# Sheet1.net
KiCad netlist of a schematic drawn in Altium Designer
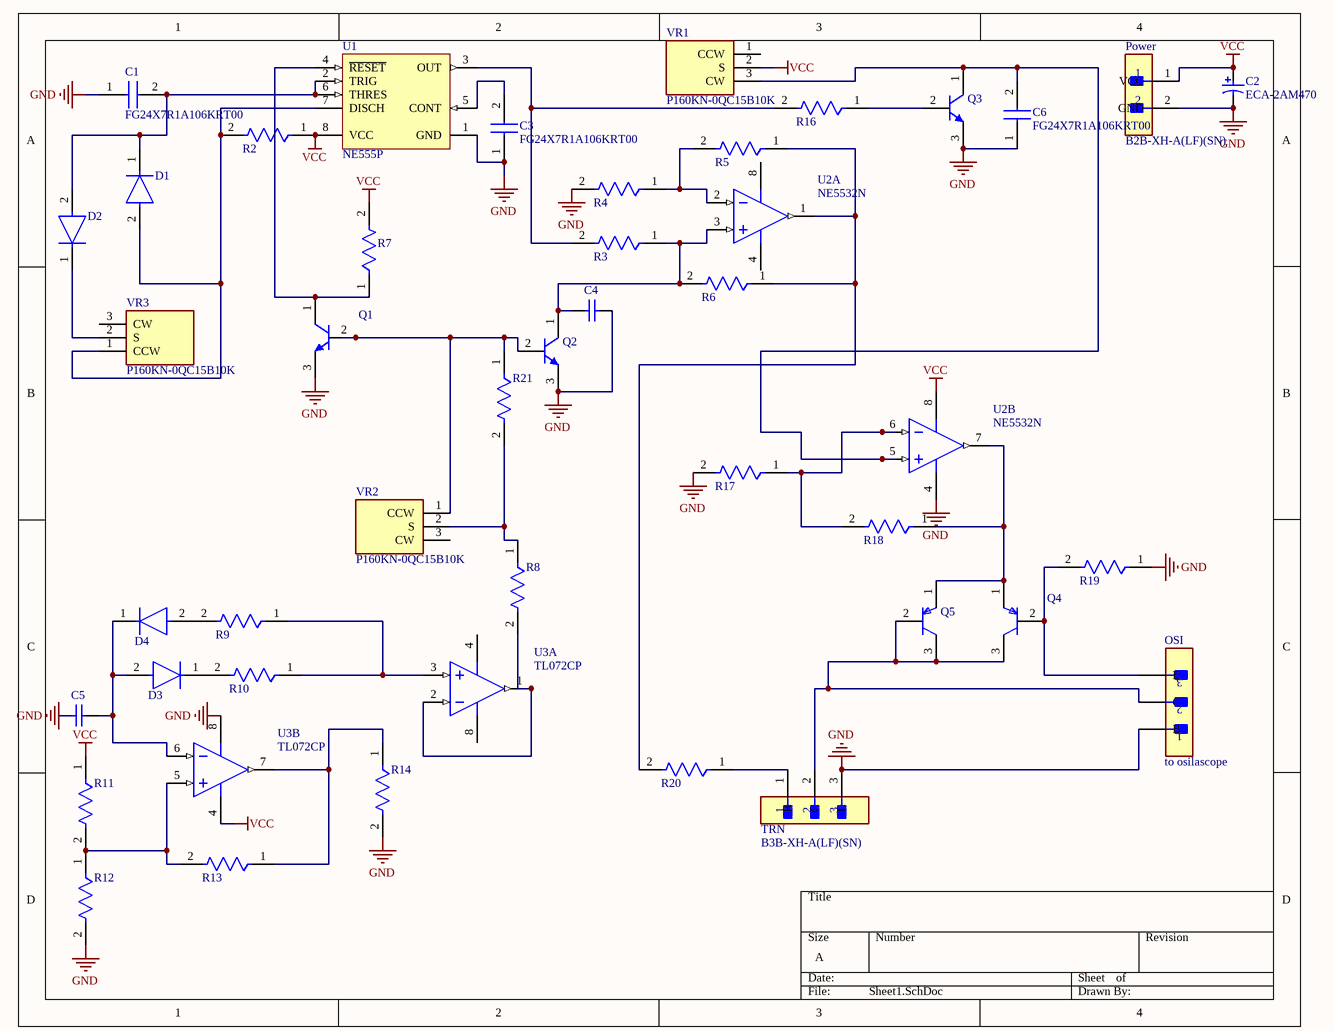
[diagram p0: Sheet1.SchDoc]

(export (version "E")
  (design (tool "Eeschema 10.0.6"))
  (components
    (comp (ref "C1")
      (value "FG24X7R1A106KRT00")
      (footprint "SamacSys:FG24")
      (description "Capacitor")
      (fields (field (name "MOUSER PART NUMBER") "810-FG24X7R1A106KRT0"))
      (libsource (lib "*") (part "FG24X7R1A106KRT00"))
    )
    (comp (ref "C2")
      (value "ECA-2AM470")
      (footprint "CAPPR65-350-1150X800X1250")
      (description "Aluminum Electrolytic Capacitor, 47 uF, +/- 20%, 100 V, -40 to 85 degC, 2-Pin THD, RoHS, Bulk")
      (libsource (lib "Altium Content Vault") (part "CAP-P-2"))
    )
    (comp (ref "C3")
      (value "FG24X7R1A106KRT00")
      (footprint "SamacSys:FG24")
      (description "Capacitor")
      (fields (field (name "MOUSER PART NUMBER") "810-FG24X7R1A106KRT0"))
      (libsource (lib "*") (part "FG24X7R1A106KRT00"))
    )
    (comp (ref "C4")
      (value "SA115C104KAR")
      (footprint "AVX-SA115C104KAR")
      (fields (field (name "TOLERANCE") "±10%") (field (name "MANUFACTURER") "AVX"))
      (libsource (lib "Altium Content Vault") (part "CAP-NP-2"))
    )
    (comp (ref "C5")
      (value "SA115C104KAR")
      (footprint "AVX-SA115C104KAR")
      (fields (field (name "TOLERANCE") "±10%") (field (name "MANUFACTURER") "AVX"))
      (libsource (lib "Altium Content Vault") (part "CAP-NP-2"))
    )
    (comp (ref "C6")
      (value "FG24X7R1A106KRT00")
      (footprint "SamacSys:FG24")
      (description "Capacitor")
      (fields (field (name "MOUSER PART NUMBER") "810-FG24X7R1A106KRT0"))
      (libsource (lib "*") (part "FG24X7R1A106KRT00"))
    )
    (comp (ref "D1")
      (value "1N4001-E3/54")
      (footprint "FP-1N4001-E3-54-MFG")
      (description "DIODE GEN PURP 50V 1A DO204AL")
      (fields (field (name "VOLTAGE") "50V"))
      (libsource (lib "Altium Content Vault") (part "d7152d700b627762746794eb795d46e"))
    )
    (comp (ref "D2")
      (value "1N4001-E3/54")
      (footprint "FP-1N4001-E3-54-MFG")
      (description "DIODE GEN PURP 50V 1A DO204AL")
      (fields (field (name "VOLTAGE") "50V"))
      (libsource (lib "Altium Content Vault") (part "d7152d700b627762746794eb795d46e"))
    )
    (comp (ref "D3")
      (value "1N4001-E3/54")
      (footprint "FP-1N4001-E3-54-MFG")
      (description "DIODE GEN PURP 50V 1A DO204AL")
      (fields (field (name "VOLTAGE") "50V"))
      (libsource (lib "Altium Content Vault") (part "d7152d700b627762746794eb795d46e"))
    )
    (comp (ref "D4")
      (value "1N4001-E3/54")
      (footprint "FP-1N4001-E3-54-MFG")
      (description "DIODE GEN PURP 50V 1A DO204AL")
      (fields (field (name "VOLTAGE") "50V"))
      (libsource (lib "Altium Content Vault") (part "d7152d700b627762746794eb795d46e"))
    )
    (comp (ref "OSI")
      (value "to osilascope")
      (footprint "FP-B3B-XH-A_LF_SN-MFG")
      (description "CONN HEADER VERT 3POS 2.5MM")
      (libsource (lib "") (part "0d3f023dd272f625e17a2be33dea85f_1"))
    )
    (comp (ref "Power")
      (value "B2B-XH-A(LF)(SN)")
      (footprint "FP-B2B-XH-A_LF_SN-MFG")
      (description "CONN HEADER VERT 2POS 2.5MM")
      (libsource (lib "Altium Content Vault") (part "3bc925449376181038e59eaffc5286c"))
    )
    (comp (ref "Q1")
      (value "P2N2222ARL1G")
      (footprint "ONSC-TO-92-3-29-11_AM_BL")
      (description "Amplifier Transistor, NPN Silicon, 3-Pin TO-92, Pb-Free, Tape and Reel")
      (fields (field (name "MANUFACTURER") "On Semiconductor"))
      (libsource (lib "Altium Content Vault") (part "ONSC-NPN-C1B2E3-3"))
    )
    (comp (ref "Q2")
      (value "P2N2222ARL1G")
      (footprint "ONSC-TO-92-3-29-11_AM_BL")
      (description "Amplifier Transistor, NPN Silicon, 3-Pin TO-92, Pb-Free, Tape and Reel")
      (fields (field (name "MANUFACTURER") "On Semiconductor"))
      (libsource (lib "Altium Content Vault") (part "ONSC-NPN-C1B2E3-3"))
    )
    (comp (ref "Q3")
      (value "P2N2222ARL1G")
      (footprint "ONSC-TO-92-3-29-11_AM_BL")
      (description "Amplifier Transistor, NPN Silicon, 3-Pin TO-92, Pb-Free, Tape and Reel")
      (fields (field (name "MANUFACTURER") "On Semiconductor"))
      (libsource (lib "Altium Content Vault") (part "ONSC-NPN-C1B2E3-3"))
    )
    (comp (ref "Q4")
      (value "2N3906TF")
      (footprint "FP-135AR-MFG")
      (description "2N3906TF Small Signal Bipolar Transistor, 0.2A I(C), 40V V(BR)CEO, 1-Element, PNP, Silicon, TO-92")
      (libsource (lib "Altium Content Vault") (part "40d2b7e180a7bcff784209620afba3e"))
    )
    (comp (ref "Q5")
      (value "2N3906TF")
      (footprint "FP-135AR-MFG")
      (description "2N3906TF Small Signal Bipolar Transistor, 0.2A I(C), 40V V(BR)CEO, 1-Element, PNP, Silicon, TO-92")
      (libsource (lib "Altium Content Vault") (part "40d2b7e180a7bcff784209620afba3e"))
    )
    (comp (ref "R2")
      (value "MRS16000C2002FCT00")
      (footprint "FP-MRS1600-MFG")
      (description "RES 20K OHM 0.4W 1% AXIAL")
      (fields (field (name "TOLERANCE") "1%"))
      (libsource (lib "Altium Content Vault") (part "1029c3af85768c4190bb7ad29bc67b5"))
    )
    (comp (ref "R3")
      (value "MRS16000C2002FCT00")
      (footprint "FP-MRS1600-MFG")
      (description "RES 20K OHM 0.4W 1% AXIAL")
      (fields (field (name "TOLERANCE") "1%"))
      (libsource (lib "Altium Content Vault") (part "1029c3af85768c4190bb7ad29bc67b5"))
    )
    (comp (ref "R4")
      (value "MRS16000C2002FCT00")
      (footprint "FP-MRS1600-MFG")
      (description "RES 20K OHM 0.4W 1% AXIAL")
      (fields (field (name "TOLERANCE") "1%"))
      (libsource (lib "Altium Content Vault") (part "1029c3af85768c4190bb7ad29bc67b5"))
    )
    (comp (ref "R5")
      (value "MRS16000C2002FCT00")
      (footprint "FP-MRS1600-MFG")
      (description "RES 20K OHM 0.4W 1% AXIAL")
      (fields (field (name "TOLERANCE") "1%"))
      (libsource (lib "Altium Content Vault") (part "1029c3af85768c4190bb7ad29bc67b5"))
    )
    (comp (ref "R6")
      (value "MRS16000C2002FCT00")
      (footprint "FP-MRS1600-MFG")
      (description "RES 20K OHM 0.4W 1% AXIAL")
      (fields (field (name "TOLERANCE") "1%"))
      (libsource (lib "Altium Content Vault") (part "1029c3af85768c4190bb7ad29bc67b5"))
    )
    (comp (ref "R7")
      (value "MRS16000C2002FCT00")
      (footprint "FP-MRS1600-MFG")
      (description "RES 20K OHM 0.4W 1% AXIAL")
      (fields (field (name "TOLERANCE") "1%"))
      (libsource (lib "Altium Content Vault") (part "1029c3af85768c4190bb7ad29bc67b5"))
    )
    (comp (ref "R8")
      (value "MRS16000C2002FCT00")
      (footprint "FP-MRS1600-MFG")
      (description "RES 20K OHM 0.4W 1% AXIAL")
      (fields (field (name "TOLERANCE") "1%"))
      (libsource (lib "Altium Content Vault") (part "1029c3af85768c4190bb7ad29bc67b5"))
    )
    (comp (ref "R9")
      (value "MRS16000C2002FCT00")
      (footprint "FP-MRS1600-MFG")
      (description "RES 20K OHM 0.4W 1% AXIAL")
      (fields (field (name "TOLERANCE") "1%"))
      (libsource (lib "Altium Content Vault") (part "1029c3af85768c4190bb7ad29bc67b5"))
    )
    (comp (ref "R10")
      (value "MRS16000C2002FCT00")
      (footprint "FP-MRS1600-MFG")
      (description "RES 20K OHM 0.4W 1% AXIAL")
      (fields (field (name "TOLERANCE") "1%"))
      (libsource (lib "Altium Content Vault") (part "1029c3af85768c4190bb7ad29bc67b5"))
    )
    (comp (ref "R11")
      (value "MRS16000C2002FCT00")
      (footprint "FP-MRS1600-MFG")
      (description "RES 20K OHM 0.4W 1% AXIAL")
      (fields (field (name "TOLERANCE") "1%"))
      (libsource (lib "Altium Content Vault") (part "1029c3af85768c4190bb7ad29bc67b5"))
    )
    (comp (ref "R12")
      (value "MRS16000C2002FCT00")
      (footprint "FP-MRS1600-MFG")
      (description "RES 20K OHM 0.4W 1% AXIAL")
      (fields (field (name "TOLERANCE") "1%"))
      (libsource (lib "Altium Content Vault") (part "1029c3af85768c4190bb7ad29bc67b5"))
    )
    (comp (ref "R13")
      (value "MRS16000C2002FCT00")
      (footprint "FP-MRS1600-MFG")
      (description "RES 20K OHM 0.4W 1% AXIAL")
      (fields (field (name "TOLERANCE") "1%"))
      (libsource (lib "Altium Content Vault") (part "1029c3af85768c4190bb7ad29bc67b5"))
    )
    (comp (ref "R14")
      (value "MRS16000C2002FCT00")
      (footprint "FP-MRS1600-MFG")
      (description "RES 20K OHM 0.4W 1% AXIAL")
      (fields (field (name "TOLERANCE") "1%"))
      (libsource (lib "Altium Content Vault") (part "1029c3af85768c4190bb7ad29bc67b5"))
    )
    (comp (ref "R16")
      (value "MRS16000C2002FCT00")
      (footprint "FP-MRS1600-MFG")
      (description "RES 20K OHM 0.4W 1% AXIAL")
      (fields (field (name "TOLERANCE") "1%"))
      (libsource (lib "Altium Content Vault") (part "1029c3af85768c4190bb7ad29bc67b5"))
    )
    (comp (ref "R17")
      (value "MRS16000C2002FCT00")
      (footprint "FP-MRS1600-MFG")
      (description "RES 20K OHM 0.4W 1% AXIAL")
      (fields (field (name "TOLERANCE") "1%"))
      (libsource (lib "Altium Content Vault") (part "1029c3af85768c4190bb7ad29bc67b5"))
    )
    (comp (ref "R18")
      (value "MRS16000C2002FCT00")
      (footprint "FP-MRS1600-MFG")
      (description "RES 20K OHM 0.4W 1% AXIAL")
      (fields (field (name "TOLERANCE") "1%"))
      (libsource (lib "Altium Content Vault") (part "1029c3af85768c4190bb7ad29bc67b5"))
    )
    (comp (ref "R19")
      (value "MRS16000C2002FCT00")
      (footprint "FP-MRS1600-MFG")
      (description "RES 20K OHM 0.4W 1% AXIAL")
      (fields (field (name "TOLERANCE") "1%"))
      (libsource (lib "Altium Content Vault") (part "1029c3af85768c4190bb7ad29bc67b5"))
    )
    (comp (ref "R20")
      (value "MRS16000C2002FCT00")
      (footprint "FP-MRS1600-MFG")
      (description "RES 20K OHM 0.4W 1% AXIAL")
      (fields (field (name "TOLERANCE") "1%"))
      (libsource (lib "Altium Content Vault") (part "1029c3af85768c4190bb7ad29bc67b5"))
    )
    (comp (ref "R21")
      (value "MRS16000C2002FCT00")
      (footprint "FP-MRS1600-MFG")
      (description "RES 20K OHM 0.4W 1% AXIAL")
      (fields (field (name "TOLERANCE") "1%"))
      (libsource (lib "Altium Content Vault") (part "1029c3af85768c4190bb7ad29bc67b5"))
    )
    (comp (ref "TRN")
      (value "B3B-XH-A(LF)(SN)")
      (footprint "FP-B3B-XH-A_LF_SN-MFG")
      (description "CONN HEADER VERT 3POS 2.5MM")
      (libsource (lib "Altium Content Vault") (part "0d3f023dd272f625e17a2be33dea85f"))
    )
    (comp (ref "U1")
      (value "NE555P")
      (footprint "P0008A")
      (description "Precision Timer, 4.5 to 16 V, 0 to 70 degC, 8-Pin DIP, Pb-Free, Tube")
      (fields (field (name "MANUFACTURER") "TexasInstruments"))
      (libsource (lib "Altium Content Vault") (part "TI-NE555-P8"))
    )
    (comp (ref "U2")
      (value "NE5532N")
      (footprint "ONSC-PDIP-8-626-05")
      (fields (field (name "MANUFACTURER") "On Semiconductor"))
      (libsource (lib "Altium Content Vault") (part "ONSC-NE5532-PDIP-8-626-05"))
    )
    (comp (ref "U3")
      (value "TL072CP")
      (footprint "P0008A")
      (fields (field (name "MANUFACTURER") "Texas Instruments"))
      (libsource (lib "Altium Content Vault") (part "TI-AMP-D6-2-8_D"))
    )
    (comp (ref "VR1")
      (value "P160KN-0QC15B10K")
      (footprint "SamacSys:P160KN0QC15B10K")
      (description "Variable Resistor")
      (fields (field (name "MOUSER PART NUMBER") "858-P160KN-0QC15B10K"))
      (libsource (lib "") (part "P160KN-0QC15B10K_1"))
    )
    (comp (ref "VR2")
      (value "P160KN-0QC15B10K")
      (footprint "SamacSys:P160KN0QC15B10K")
      (description "Variable Resistor")
      (fields (field (name "MOUSER PART NUMBER") "858-P160KN-0QC15B10K"))
      (libsource (lib "") (part "P160KN-0QC15B10K_1"))
    )
    (comp (ref "VR3")
      (value "P160KN-0QC15B10K")
      (footprint "SamacSys:P160KN0QC15B10K")
      (description "Variable Resistor")
      (fields (field (name "MOUSER PART NUMBER") "858-P160KN-0QC15B10K"))
      (libsource (lib "*") (part "P160KN-0QC15B10K"))
    )
  )
  (nets
    (net (code "1") (name "GND") (class "Default")
      (node (ref "C1") (pin "1") (pinfunction "1_1") (pintype "passive"))
      (node (ref "C2") (pin "2") (pinfunction "2_2") (pintype "passive"))
      (node (ref "C3") (pin "1") (pinfunction "1_1") (pintype "passive"))
      (node (ref "C4") (pin "2") (pinfunction "2_2") (pintype "passive"))
      (node (ref "C5") (pin "1") (pinfunction "1_1") (pintype "passive"))
      (node (ref "C6") (pin "1") (pinfunction "1_1") (pintype "passive"))
      (node (ref "OSI") (pin "1") (pinfunction "B_1") (pintype "passive"))
      (node (ref "Power") (pin "2") (pinfunction "GND_2") (pintype "passive"))
      (node (ref "Q1") (pin "3") (pinfunction "E_3") (pintype "passive"))
      (node (ref "Q2") (pin "3") (pinfunction "E_3") (pintype "passive"))
      (node (ref "Q3") (pin "3") (pinfunction "E_3") (pintype "passive"))
      (node (ref "R12") (pin "2") (pinfunction "2_2") (pintype "passive"))
      (node (ref "R14") (pin "2") (pinfunction "2_2") (pintype "passive"))
      (node (ref "R17") (pin "2") (pinfunction "2_2") (pintype "passive"))
      (node (ref "R19") (pin "1") (pinfunction "1_1") (pintype "passive"))
      (node (ref "R4") (pin "2") (pinfunction "2_2") (pintype "passive"))
      (node (ref "TRN") (pin "3") (pinfunction "E_3") (pintype "passive"))
      (node (ref "U1") (pin "1") (pinfunction "GND_1") (pintype "power_in"))
      (node (ref "U2") (pin "4") (pinfunction "V-_4") (pintype "power_in"))
      (node (ref "U3") (pin "8") (pinfunction "VCC+_8") (pintype "power_in"))
    )
    (net (code "2") (name "Net-(D1-A)") (class "Default")
      (node (ref "D1") (pin "2") (pinfunction "A_2") (pintype "passive"))
      (node (ref "R2") (pin "2") (pinfunction "2_2") (pintype "passive"))
      (node (ref "U1") (pin "7") (pinfunction "DISCH_7") (pintype "open_collector"))
      (node (ref "VR3") (pin "1") (pinfunction "CCW_1") (pintype "passive"))
    )
    (net (code "3") (name "Net-(D1-C)") (class "Default")
      (node (ref "C1") (pin "2") (pinfunction "2_2") (pintype "passive"))
      (node (ref "D1") (pin "1") (pinfunction "C_1") (pintype "passive"))
      (node (ref "D2") (pin "2") (pinfunction "A_2") (pintype "passive"))
      (node (ref "U1") (pin "2") (pinfunction "TRIG_2") (pintype "input"))
      (node (ref "U1") (pin "6") (pinfunction "THRES_6") (pintype "input"))
    )
    (net (code "4") (name "Net-(D2-C)") (class "Default")
      (node (ref "D2") (pin "1") (pinfunction "C_1") (pintype "passive"))
      (node (ref "VR3") (pin "2") (pinfunction "S_2") (pintype "passive"))
    )
    (net (code "5") (name "Net-(D3-A)") (class "Default")
      (node (ref "C5") (pin "2") (pinfunction "2_2") (pintype "passive"))
      (node (ref "D3") (pin "2") (pinfunction "A_2") (pintype "passive"))
      (node (ref "D4") (pin "1") (pinfunction "C_1") (pintype "passive"))
      (node (ref "U3") (pin "6") (pinfunction "IN2-_6") (pintype "input"))
    )
    (net (code "6") (name "Net-(D3-C)") (class "Default")
      (node (ref "D3") (pin "1") (pinfunction "C_1") (pintype "passive"))
      (node (ref "R10") (pin "2") (pinfunction "2_2") (pintype "passive"))
    )
    (net (code "7") (name "Net-(D4-A)") (class "Default")
      (node (ref "D4") (pin "2") (pinfunction "A_2") (pintype "passive"))
      (node (ref "R9") (pin "2") (pinfunction "2_2") (pintype "passive"))
    )
    (net (code "8") (name "Net-(OSI-C)") (class "Default")
      (node (ref "OSI") (pin "2") (pinfunction "C_2") (pintype "passive"))
      (node (ref "Q4") (pin "3") (pinfunction "C_3") (pintype "passive"))
      (node (ref "Q5") (pin "2") (pinfunction "B_2") (pintype "passive"))
      (node (ref "Q5") (pin "3") (pinfunction "C_3") (pintype "passive"))
      (node (ref "TRN") (pin "2") (pinfunction "C_2") (pintype "passive"))
    )
    (net (code "9") (name "Net-(OSI-E)") (class "Default")
      (node (ref "OSI") (pin "3") (pinfunction "E_3") (pintype "passive"))
      (node (ref "Q4") (pin "2") (pinfunction "B_2") (pintype "passive"))
      (node (ref "R19") (pin "2") (pinfunction "2_2") (pintype "passive"))
    )
    (net (code "10") (name "Net-(Q1-B)") (class "Default")
      (node (ref "Q1") (pin "2") (pinfunction "B_2") (pintype "passive"))
      (node (ref "Q2") (pin "2") (pinfunction "B_2") (pintype "passive"))
      (node (ref "R21") (pin "1") (pinfunction "1_1") (pintype "passive"))
      (node (ref "VR2") (pin "1") (pinfunction "CCW_1") (pintype "passive"))
    )
    (net (code "11") (name "Net-(Q1-C)") (class "Default")
      (node (ref "Q1") (pin "1") (pinfunction "C_1") (pintype "passive"))
      (node (ref "R7") (pin "1") (pinfunction "1_1") (pintype "passive"))
      (node (ref "U1") (pin "4") (pinfunction "~{RESET}_4") (pintype "input"))
    )
    (net (code "12") (name "Net-(Q2-C)") (class "Default")
      (node (ref "C4") (pin "1") (pinfunction "1_1") (pintype "passive"))
      (node (ref "Q2") (pin "1") (pinfunction "C_1") (pintype "passive"))
      (node (ref "R3") (pin "1") (pinfunction "1_1") (pintype "passive"))
      (node (ref "R6") (pin "2") (pinfunction "2_2") (pintype "passive"))
      (node (ref "U2") (pin "3") (pinfunction "INA+_3") (pintype "input"))
    )
    (net (code "13") (name "Net-(Q3-B)") (class "Default")
      (node (ref "Q3") (pin "2") (pinfunction "B_2") (pintype "passive"))
      (node (ref "R16") (pin "1") (pinfunction "1_1") (pintype "passive"))
    )
    (net (code "14") (name "Net-(Q3-C)") (class "Default")
      (node (ref "C6") (pin "2") (pinfunction "2_2") (pintype "passive"))
      (node (ref "Q3") (pin "1") (pinfunction "C_1") (pintype "passive"))
      (node (ref "U2") (pin "5") (pinfunction "INB+_5") (pintype "input"))
      (node (ref "VR1") (pin "3") (pinfunction "CW_3") (pintype "passive"))
    )
    (net (code "15") (name "Net-(Q4-E)") (class "Default")
      (node (ref "Q4") (pin "1") (pinfunction "E_1") (pintype "passive"))
      (node (ref "Q5") (pin "1") (pinfunction "E_1") (pintype "passive"))
      (node (ref "R18") (pin "1") (pinfunction "1_1") (pintype "passive"))
      (node (ref "U2") (pin "7") (pinfunction "OUTB_7") (pintype "output"))
    )
    (net (code "16") (name "Net-(TRN-B)") (class "Default")
      (node (ref "R20") (pin "1") (pinfunction "1_1") (pintype "passive"))
      (node (ref "TRN") (pin "1") (pinfunction "B_1") (pintype "passive"))
    )
    (net (code "17") (name "Net-(U1-CONT)") (class "Default")
      (node (ref "C3") (pin "2") (pinfunction "2_2") (pintype "passive"))
      (node (ref "U1") (pin "5") (pinfunction "CONT_5") (pintype "input"))
    )
    (net (code "18") (name "Net-(U1-OUT)") (class "Default")
      (node (ref "R16") (pin "2") (pinfunction "2_2") (pintype "passive"))
      (node (ref "R3") (pin "2") (pinfunction "2_2") (pintype "passive"))
      (node (ref "U1") (pin "3") (pinfunction "OUT_3") (pintype "output"))
    )
    (net (code "19") (name "Net-(U2A-INA-)") (class "Default")
      (node (ref "R4") (pin "1") (pinfunction "1_1") (pintype "passive"))
      (node (ref "R5") (pin "2") (pinfunction "2_2") (pintype "passive"))
      (node (ref "U2") (pin "2") (pinfunction "INA-_2") (pintype "input"))
    )
    (net (code "20") (name "Net-(U2A-OUTA)") (class "Default")
      (node (ref "R20") (pin "2") (pinfunction "2_2") (pintype "passive"))
      (node (ref "R5") (pin "1") (pinfunction "1_1") (pintype "passive"))
      (node (ref "R6") (pin "1") (pinfunction "1_1") (pintype "passive"))
      (node (ref "U2") (pin "1") (pinfunction "OUTA_1") (pintype "output"))
    )
    (net (code "21") (name "Net-(U2B-INB-)") (class "Default")
      (node (ref "R17") (pin "1") (pinfunction "1_1") (pintype "passive"))
      (node (ref "R18") (pin "2") (pinfunction "2_2") (pintype "passive"))
      (node (ref "U2") (pin "6") (pinfunction "INB-_6") (pintype "input"))
    )
    (net (code "22") (name "Net-(U3A-IN1+)") (class "Default")
      (node (ref "R10") (pin "1") (pinfunction "1_1") (pintype "passive"))
      (node (ref "R9") (pin "1") (pinfunction "1_1") (pintype "passive"))
      (node (ref "U3") (pin "3") (pinfunction "IN1+_3") (pintype "input"))
    )
    (net (code "23") (name "Net-(U3A-IN1-)") (class "Default")
      (node (ref "R8") (pin "2") (pinfunction "2_2") (pintype "passive"))
      (node (ref "U3") (pin "1") (pinfunction "OUT1_1") (pintype "output"))
      (node (ref "U3") (pin "2") (pinfunction "IN1-_2") (pintype "input"))
    )
    (net (code "24") (name "Net-(U3B-IN2+)") (class "Default")
      (node (ref "R11") (pin "2") (pinfunction "2_2") (pintype "passive"))
      (node (ref "R12") (pin "1") (pinfunction "1_1") (pintype "passive"))
      (node (ref "R13") (pin "2") (pinfunction "2_2") (pintype "passive"))
      (node (ref "U3") (pin "5") (pinfunction "IN2+_5") (pintype "input"))
    )
    (net (code "25") (name "Net-(U3B-OUT2)") (class "Default")
      (node (ref "R13") (pin "1") (pinfunction "1_1") (pintype "passive"))
      (node (ref "R14") (pin "1") (pinfunction "1_1") (pintype "passive"))
      (node (ref "U3") (pin "7") (pinfunction "OUT2_7") (pintype "output"))
    )
    (net (code "26") (name "Net-(VR2-S)") (class "Default")
      (node (ref "R21") (pin "2") (pinfunction "2_2") (pintype "passive"))
      (node (ref "R8") (pin "1") (pinfunction "1_1") (pintype "passive"))
      (node (ref "VR2") (pin "2") (pinfunction "S_2") (pintype "passive"))
    )
    (net (code "27") (name "VCC") (class "Default")
      (node (ref "C2") (pin "1") (pinfunction "1_1") (pintype "passive"))
      (node (ref "Power") (pin "1") (pinfunction "VCC_1") (pintype "passive"))
      (node (ref "R11") (pin "1") (pinfunction "1_1") (pintype "passive"))
      (node (ref "R2") (pin "1") (pinfunction "1_1") (pintype "passive"))
      (node (ref "R7") (pin "2") (pinfunction "2_2") (pintype "passive"))
      (node (ref "U1") (pin "8") (pinfunction "VCC_8") (pintype "power_in"))
      (node (ref "U2") (pin "8") (pinfunction "V+_8") (pintype "power_in"))
      (node (ref "U3") (pin "4") (pinfunction "VCC-_4") (pintype "power_in"))
      (node (ref "VR1") (pin "2") (pinfunction "S_2") (pintype "passive"))
    )
    (net (code "28") (name "unconnected-(U2A-V+-Pad8)") (class "Default")
      (node (ref "U2") (pin "8") (pinfunction "V+_8") (pintype "power_in"))
    )
    (net (code "29") (name "unconnected-(U2A-V--Pad4)") (class "Default")
      (node (ref "U2") (pin "4") (pinfunction "V-_4") (pintype "power_in"))
    )
    (net (code "30") (name "unconnected-(U3A-VCC+-Pad8)") (class "Default")
      (node (ref "U3") (pin "8") (pinfunction "VCC+_8") (pintype "power_in"))
    )
    (net (code "31") (name "unconnected-(U3A-VCC--Pad4)") (class "Default")
      (node (ref "U3") (pin "4") (pinfunction "VCC-_4") (pintype "power_in"))
    )
    (net (code "32") (name "unconnected-(VR1-CCW-Pad1)") (class "Default")
      (node (ref "VR1") (pin "1") (pinfunction "CCW_1") (pintype "passive"))
    )
    (net (code "33") (name "unconnected-(VR2-CW-Pad3)") (class "Default")
      (node (ref "VR2") (pin "3") (pinfunction "CW_3") (pintype "passive"))
    )
    (net (code "34") (name "unconnected-(VR3-CW-Pad3)") (class "Default")
      (node (ref "VR3") (pin "3") (pinfunction "CW_3") (pintype "passive"))
    )
  )
)
